# RatDBS.net
KiCad netlist of a schematic drawn in EAGLE
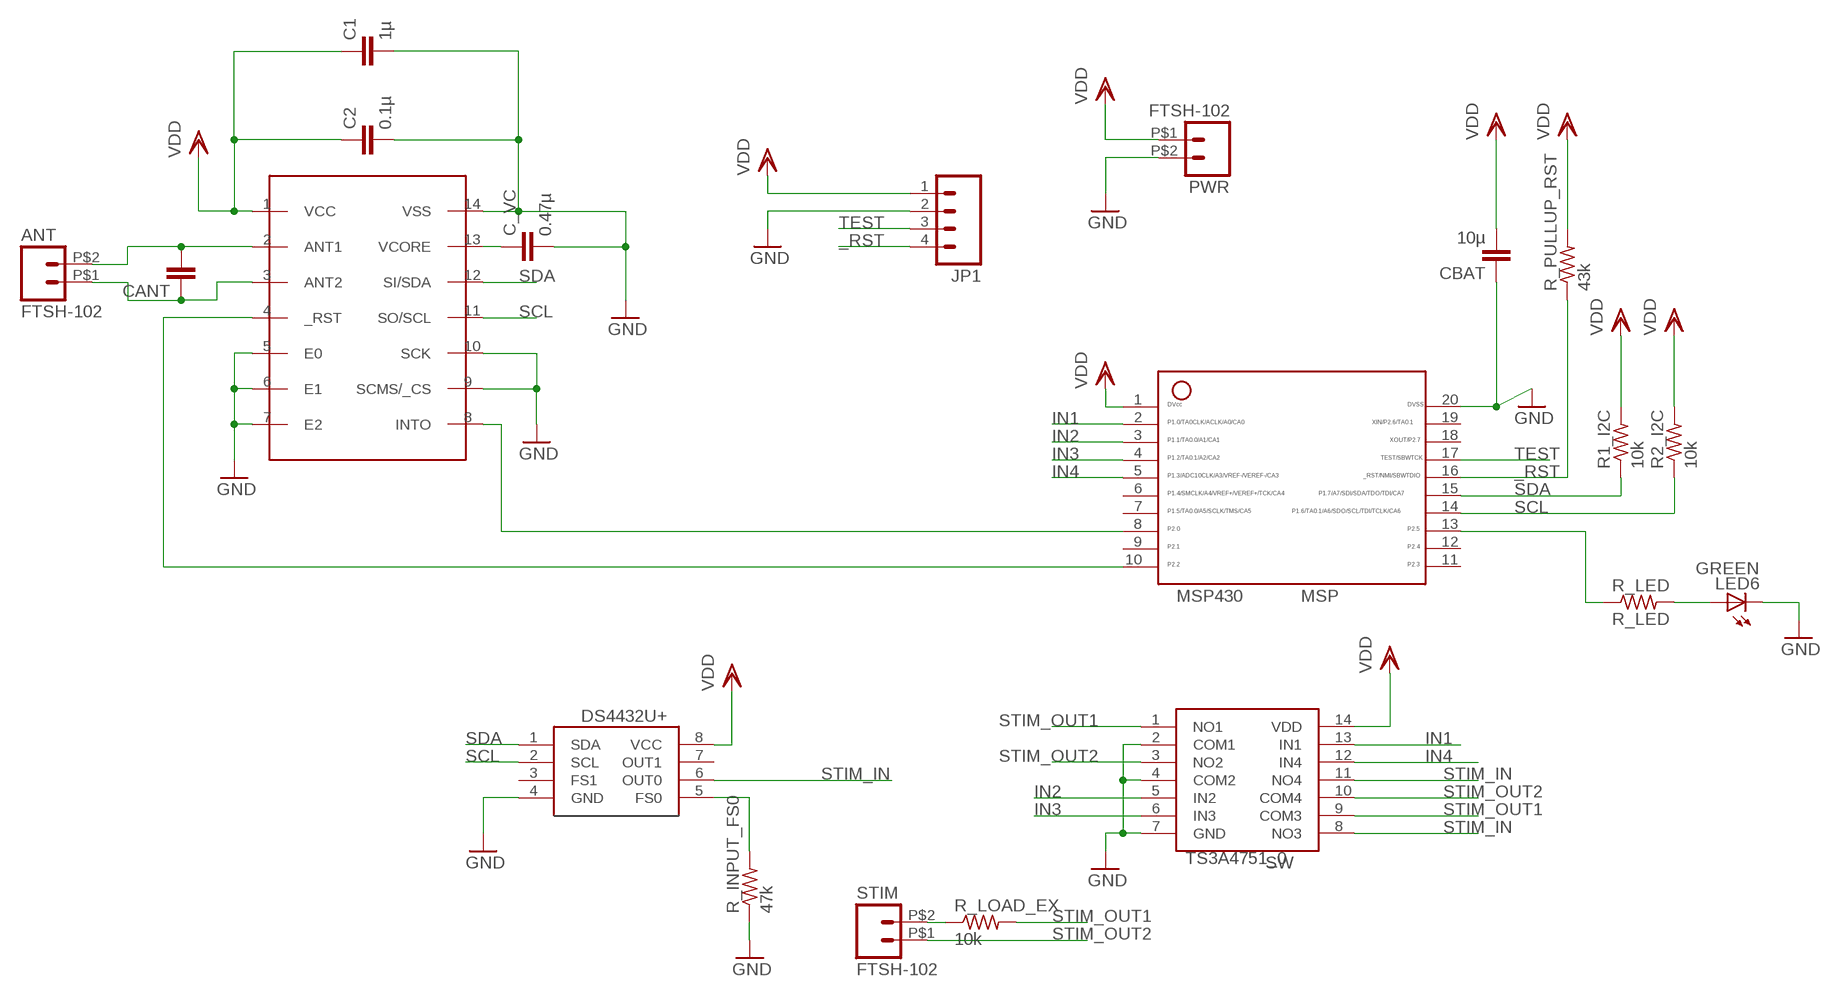
[diagram p0: schematic, sheet 1]

(export (version "E")
  (design (tool "Eeschema 10.0.6"))
  (components
    (comp (ref "ANT")
      (value "FTSH-102")
      (footprint "eagle-import:FTSH-102-DH")
      (libsource (lib "eagle-import") (part "FTSH-102"))
    )
    (comp (ref "C1")
      (value "1µ")
      (footprint "eagle-import:C0603")
      (libsource (lib "eagle-import") (part "C-EUC0603"))
    )
    (comp (ref "C2")
      (value "0.1µ")
      (footprint "eagle-import:C0603")
      (libsource (lib "eagle-import") (part "C-EUC0603"))
    )
    (comp (ref "CANT")
      (value "C-EUC0603")
      (footprint "eagle-import:C0603")
      (libsource (lib "eagle-import") (part "C-EUC0603"))
    )
    (comp (ref "CBAT")
      (value "10µ")
      (footprint "eagle-import:C0603")
      (libsource (lib "eagle-import") (part "C-EUC0603"))
    )
    (comp (ref "C_VC")
      (value "0.47µ")
      (footprint "eagle-import:C0603")
      (libsource (lib "eagle-import") (part "C-EUC0603"))
    )
    (comp (ref "DS4432U+")
      (value "DS4432U+")
      (footprint "eagle-import:8_PIN")
      (libsource (lib "eagle-import") (part "DS4432U+"))
    )
    (comp (ref "JP1")
      (value "M041.27MM")
      (footprint "eagle-import:1X04-1.27MM")
      (libsource (lib "eagle-import") (part "M041.27MM"))
    )
    (comp (ref "LED6")
      (value "GREEN")
      (footprint "eagle-import:LED-1206")
      (libsource (lib "eagle-import") (part "LED1206"))
    )
    (comp (ref "MSP430")
      (value "MSP")
      (footprint "eagle-import:20_PIN")
      (libsource (lib "eagle-import") (part "MSP430"))
    )
    (comp (ref "PWR")
      (value "FTSH-102")
      (footprint "eagle-import:FTSH-102-DH")
      (libsource (lib "eagle-import") (part "FTSH-102"))
    )
    (comp (ref "R1_I2C")
      (value "10k")
      (footprint "eagle-import:R0603")
      (libsource (lib "eagle-import") (part "R-US_R0603"))
    )
    (comp (ref "R2_I2C")
      (value "10k")
      (footprint "eagle-import:R0603")
      (libsource (lib "eagle-import") (part "R-US_R0603"))
    )
    (comp (ref "R_INPUT_FS0")
      (value "47k")
      (footprint "eagle-import:R0603")
      (libsource (lib "eagle-import") (part "R-US_R0603"))
    )
    (comp (ref "R_LED")
      (value "R_LED")
      (footprint "eagle-import:R0603")
      (libsource (lib "eagle-import") (part "R-US_R0603"))
    )
    (comp (ref "R_LOAD_EX")
      (value "10k")
      (footprint "eagle-import:R0603")
      (libsource (lib "eagle-import") (part "R-US_R0603"))
    )
    (comp (ref "R_PULLUP_RST")
      (value "43k")
      (footprint "eagle-import:R0603")
      (libsource (lib "eagle-import") (part "R-US_R0603"))
    )
    (comp (ref "STIM")
      (value "FTSH-102")
      (footprint "eagle-import:FTSH-102-DH")
      (libsource (lib "eagle-import") (part "FTSH-102"))
    )
    (comp (ref "TS3A4751_0")
      (value "SW")
      (footprint "eagle-import:14_PIN")
      (libsource (lib "eagle-import") (part "TS3A4751"))
    )
    (comp (ref "U$1")
      (value "RF")
      (footprint "eagle-import:PW_R-PDSO-G14")
      (libsource (lib "eagle-import") (part "RF430CL330H"))
    )
  )
  (nets
    (net (code "1") (name "/IN1") (class "Default")
      (node (ref "MSP430") (pin "2") (pinfunction "2_2") (pintype "bidirectional"))
      (node (ref "TS3A4751_0") (pin "13") (pinfunction "IN1_13") (pintype "bidirectional"))
    )
    (net (code "2") (name "/IN2") (class "Default")
      (node (ref "MSP430") (pin "3") (pinfunction "3_3") (pintype "bidirectional"))
      (node (ref "TS3A4751_0") (pin "5") (pinfunction "IN2_5") (pintype "bidirectional"))
    )
    (net (code "3") (name "/IN3") (class "Default")
      (node (ref "MSP430") (pin "4") (pinfunction "4_4") (pintype "bidirectional"))
      (node (ref "TS3A4751_0") (pin "6") (pinfunction "IN3_6") (pintype "bidirectional"))
    )
    (net (code "4") (name "/IN4") (class "Default")
      (node (ref "MSP430") (pin "5") (pinfunction "5_5") (pintype "bidirectional"))
      (node (ref "TS3A4751_0") (pin "12") (pinfunction "IN4_12") (pintype "bidirectional"))
    )
    (net (code "5") (name "/SCL") (class "Default")
      (node (ref "DS4432U+") (pin "2") (pinfunction "SCL_2") (pintype "bidirectional"))
      (node (ref "MSP430") (pin "14") (pinfunction "14_14") (pintype "bidirectional"))
      (node (ref "R2_I2C") (pin "1") (pinfunction "1_1") (pintype "passive"))
      (node (ref "U$1") (pin "11") (pinfunction "SO/SCL_11") (pintype "bidirectional"))
    )
    (net (code "6") (name "/SDA") (class "Default")
      (node (ref "DS4432U+") (pin "1") (pinfunction "SDA_1") (pintype "bidirectional"))
      (node (ref "MSP430") (pin "15") (pinfunction "15_15") (pintype "bidirectional"))
      (node (ref "R1_I2C") (pin "1") (pinfunction "1_1") (pintype "passive"))
      (node (ref "U$1") (pin "12") (pinfunction "SI/SDA_12") (pintype "bidirectional"))
    )
    (net (code "7") (name "/STIM_IN") (class "Default")
      (node (ref "DS4432U+") (pin "6") (pinfunction "OUT0_6") (pintype "bidirectional"))
      (node (ref "TS3A4751_0") (pin "11") (pinfunction "NO4_11") (pintype "bidirectional"))
      (node (ref "TS3A4751_0") (pin "8") (pinfunction "NO3_8") (pintype "bidirectional"))
    )
    (net (code "8") (name "/STIM_OUT1") (class "Default")
      (node (ref "R_LOAD_EX") (pin "2") (pinfunction "2_2") (pintype "passive"))
      (node (ref "TS3A4751_0") (pin "1") (pinfunction "NO1_1") (pintype "bidirectional"))
      (node (ref "TS3A4751_0") (pin "9") (pinfunction "COM3_9") (pintype "bidirectional"))
    )
    (net (code "9") (name "/STIM_OUT2") (class "Default")
      (node (ref "STIM") (pin "P$1") (pinfunction "1_P$1") (pintype "passive"))
      (node (ref "TS3A4751_0") (pin "10") (pinfunction "COM4_10") (pintype "bidirectional"))
      (node (ref "TS3A4751_0") (pin "3") (pinfunction "NO2_3") (pintype "bidirectional"))
    )
    (net (code "10") (name "/TEST") (class "Default")
      (node (ref "JP1") (pin "3") (pinfunction "3_3") (pintype "passive"))
      (node (ref "MSP430") (pin "17") (pinfunction "17_17") (pintype "bidirectional"))
    )
    (net (code "11") (name "/_RST") (class "Default")
      (node (ref "JP1") (pin "4") (pinfunction "4_4") (pintype "passive"))
      (node (ref "MSP430") (pin "16") (pinfunction "16_16") (pintype "bidirectional"))
      (node (ref "R_PULLUP_RST") (pin "1") (pinfunction "1_1") (pintype "passive"))
    )
    (net (code "12") (name "GND") (class "Default")
      (node (ref "C1") (pin "2") (pinfunction "2_2") (pintype "passive"))
      (node (ref "C2") (pin "2") (pinfunction "2_2") (pintype "passive"))
      (node (ref "CBAT") (pin "1") (pinfunction "1_1") (pintype "passive"))
      (node (ref "C_VC") (pin "2") (pinfunction "2_2") (pintype "passive"))
      (node (ref "DS4432U+") (pin "4") (pinfunction "GND_4") (pintype "power_in"))
      (node (ref "JP1") (pin "2") (pinfunction "2_2") (pintype "passive"))
      (node (ref "LED6") (pin "C") (pinfunction "C_C") (pintype "passive"))
      (node (ref "MSP430") (pin "20") (pinfunction "20_20") (pintype "bidirectional"))
      (node (ref "PWR") (pin "P$2") (pinfunction "2_P$2") (pintype "passive"))
      (node (ref "R_INPUT_FS0") (pin "1") (pinfunction "1_1") (pintype "passive"))
      (node (ref "TS3A4751_0") (pin "2") (pinfunction "COM1_2") (pintype "bidirectional"))
      (node (ref "TS3A4751_0") (pin "4") (pinfunction "COM2_4") (pintype "bidirectional"))
      (node (ref "TS3A4751_0") (pin "7") (pinfunction "GND_7") (pintype "bidirectional"))
      (node (ref "U$1") (pin "10") (pinfunction "SCK_10") (pintype "bidirectional"))
      (node (ref "U$1") (pin "14") (pinfunction "VSS_14") (pintype "power_in"))
      (node (ref "U$1") (pin "5") (pinfunction "E0_5") (pintype "bidirectional"))
      (node (ref "U$1") (pin "6") (pinfunction "E1_6") (pintype "bidirectional"))
      (node (ref "U$1") (pin "7") (pinfunction "E2_7") (pintype "bidirectional"))
      (node (ref "U$1") (pin "9") (pinfunction "SCMS/_CS_9") (pintype "bidirectional"))
    )
    (net (code "13") (name "Net-(ANT-1)") (class "Default")
      (node (ref "ANT") (pin "P$1") (pinfunction "1_P$1") (pintype "passive"))
      (node (ref "CANT") (pin "1") (pinfunction "1_1") (pintype "passive"))
      (node (ref "U$1") (pin "3") (pinfunction "ANT2_3") (pintype "bidirectional"))
    )
    (net (code "14") (name "Net-(ANT-2)") (class "Default")
      (node (ref "ANT") (pin "P$2") (pinfunction "2_P$2") (pintype "passive"))
      (node (ref "CANT") (pin "2") (pinfunction "2_2") (pintype "passive"))
      (node (ref "U$1") (pin "2") (pinfunction "ANT1_2") (pintype "bidirectional"))
    )
    (net (code "15") (name "Net-(DS4432U+-FS0)") (class "Default")
      (node (ref "DS4432U+") (pin "5") (pinfunction "FS0_5") (pintype "bidirectional"))
      (node (ref "R_INPUT_FS0") (pin "2") (pinfunction "2_2") (pintype "passive"))
    )
    (net (code "16") (name "Net-(LED6-PadA)") (class "Default")
      (node (ref "LED6") (pin "A") (pinfunction "A_A") (pintype "passive"))
      (node (ref "R_LED") (pin "2") (pinfunction "2_2") (pintype "passive"))
    )
    (net (code "17") (name "Net-(MSP430-Pad13)") (class "Default")
      (node (ref "MSP430") (pin "13") (pinfunction "13_13") (pintype "bidirectional"))
      (node (ref "R_LED") (pin "1") (pinfunction "1_1") (pintype "passive"))
    )
    (net (code "18") (name "Net-(STIM-2)") (class "Default")
      (node (ref "R_LOAD_EX") (pin "1") (pinfunction "1_1") (pintype "passive"))
      (node (ref "STIM") (pin "P$2") (pinfunction "2_P$2") (pintype "passive"))
    )
    (net (code "19") (name "Net-(U$1-INTO)") (class "Default")
      (node (ref "MSP430") (pin "8") (pinfunction "8_8") (pintype "bidirectional"))
      (node (ref "U$1") (pin "8") (pinfunction "INTO_8") (pintype "bidirectional"))
    )
    (net (code "20") (name "Net-(U$1-VCORE)") (class "Default")
      (node (ref "C_VC") (pin "1") (pinfunction "1_1") (pintype "passive"))
      (node (ref "U$1") (pin "13") (pinfunction "VCORE_13") (pintype "bidirectional"))
    )
    (net (code "21") (name "Net-(U$1-_RST)") (class "Default")
      (node (ref "MSP430") (pin "10") (pinfunction "10_10") (pintype "bidirectional"))
      (node (ref "U$1") (pin "4") (pinfunction "_RST_4") (pintype "bidirectional"))
    )
    (net (code "22") (name "VDD") (class "Default")
      (node (ref "C1") (pin "1") (pinfunction "1_1") (pintype "passive"))
      (node (ref "C2") (pin "1") (pinfunction "1_1") (pintype "passive"))
      (node (ref "CBAT") (pin "2") (pinfunction "2_2") (pintype "passive"))
      (node (ref "DS4432U+") (pin "8") (pinfunction "VCC_8") (pintype "power_in"))
      (node (ref "JP1") (pin "1") (pinfunction "1_1") (pintype "passive"))
      (node (ref "MSP430") (pin "1") (pinfunction "1_1") (pintype "bidirectional"))
      (node (ref "PWR") (pin "P$1") (pinfunction "1_P$1") (pintype "passive"))
      (node (ref "R1_I2C") (pin "2") (pinfunction "2_2") (pintype "passive"))
      (node (ref "R2_I2C") (pin "2") (pinfunction "2_2") (pintype "passive"))
      (node (ref "R_PULLUP_RST") (pin "2") (pinfunction "2_2") (pintype "passive"))
      (node (ref "TS3A4751_0") (pin "14") (pinfunction "VDD_14") (pintype "bidirectional"))
      (node (ref "U$1") (pin "1") (pinfunction "VCC_1") (pintype "power_in"))
    )
    (net (code "23") (name "unconnected-(DS4432U+-FS1-Pad3)") (class "Default")
      (node (ref "DS4432U+") (pin "3") (pinfunction "FS1_3") (pintype "bidirectional"))
    )
    (net (code "24") (name "unconnected-(DS4432U+-OUT1-Pad7)") (class "Default")
      (node (ref "DS4432U+") (pin "7") (pinfunction "OUT1_7") (pintype "bidirectional"))
    )
    (net (code "25") (name "unconnected-(MSP430-Pad6)") (class "Default")
      (node (ref "MSP430") (pin "6") (pinfunction "6_6") (pintype "bidirectional"))
    )
    (net (code "26") (name "unconnected-(MSP430-Pad7)") (class "Default")
      (node (ref "MSP430") (pin "7") (pinfunction "7_7") (pintype "bidirectional"))
    )
    (net (code "27") (name "unconnected-(MSP430-Pad9)") (class "Default")
      (node (ref "MSP430") (pin "9") (pinfunction "9_9") (pintype "bidirectional"))
    )
    (net (code "28") (name "unconnected-(MSP430-Pad11)") (class "Default")
      (node (ref "MSP430") (pin "11") (pinfunction "11_11") (pintype "bidirectional"))
    )
    (net (code "29") (name "unconnected-(MSP430-Pad12)") (class "Default")
      (node (ref "MSP430") (pin "12") (pinfunction "12_12") (pintype "bidirectional"))
    )
    (net (code "30") (name "unconnected-(MSP430-Pad18)") (class "Default")
      (node (ref "MSP430") (pin "18") (pinfunction "18_18") (pintype "bidirectional"))
    )
    (net (code "31") (name "unconnected-(MSP430-Pad19)") (class "Default")
      (node (ref "MSP430") (pin "19") (pinfunction "19_19") (pintype "bidirectional"))
    )
  )
)
